# SenseGrain_v0_1.net
KiCad netlist of a schematic drawn in EAGLE
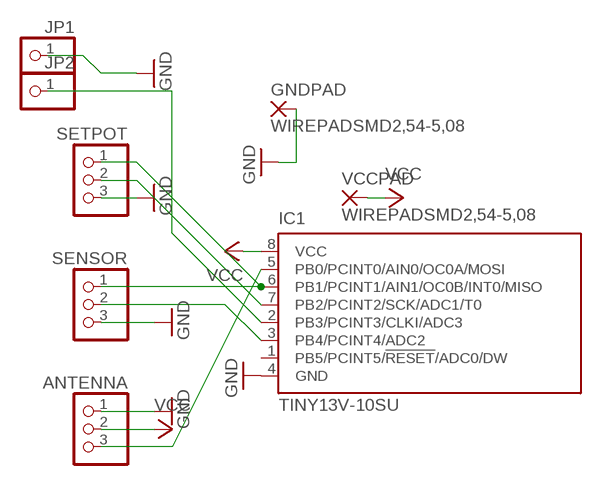
[diagram p0: schematic, sheet 1]

(export (version "E")
  (design (tool "Eeschema 10.0.6"))
  (components
    (comp (ref "ANTENNA")
      (value "PINHD-1X3CB")
      (footprint "eagle-import:1X03-CLEANBIG")
      (libsource (lib "eagle-import") (part "PINHD-1X3CB"))
    )
    (comp (ref "GNDPAD")
      (value "WIREPADSMD2,54-5,08")
      (footprint "eagle-import:SMD2,54-5,08")
      (libsource (lib "eagle-import") (part "WIREPADSMD2,54-5,08"))
    )
    (comp (ref "IC1")
      (value "TINY13V-10SU")
      (footprint "eagle-import:8S2")
      (fields (field (name "MPN") "ATTINY13V-10SU"))
      (libsource (lib "eagle-import") (part "TINY13SUV-10"))
    )
    (comp (ref "JP1")
      (value "PINHD-1X1")
      (footprint "eagle-import:1X01")
      (libsource (lib "eagle-import") (part "PINHD-1X1"))
    )
    (comp (ref "JP2")
      (value "PINHD-1X1")
      (footprint "eagle-import:1X01")
      (libsource (lib "eagle-import") (part "PINHD-1X1"))
    )
    (comp (ref "SENSOR")
      (value "PINHD-1X3CB")
      (footprint "eagle-import:1X03-CLEANBIG")
      (libsource (lib "eagle-import") (part "PINHD-1X3CB"))
    )
    (comp (ref "SETPOT")
      (value "PINHD-1X3CB")
      (footprint "eagle-import:1X03-CLEANBIG")
      (libsource (lib "eagle-import") (part "PINHD-1X3CB"))
    )
    (comp (ref "VCCPAD")
      (value "WIREPADSMD2,54-5,08")
      (footprint "eagle-import:SMD2,54-5,08")
      (libsource (lib "eagle-import") (part "WIREPADSMD2,54-5,08"))
    )
  )
  (nets
    (net (code "1") (name "GND") (class "Default")
      (node (ref "ANTENNA") (pin "1") (pinfunction "1_1") (pintype "passive"))
      (node (ref "GNDPAD") (pin "1") (pinfunction "P_1") (pintype "passive"))
      (node (ref "IC1") (pin "4") (pinfunction "GND_4") (pintype "power_in"))
      (node (ref "JP1") (pin "1") (pinfunction "1_1") (pintype "passive"))
      (node (ref "SENSOR") (pin "3") (pinfunction "3_3") (pintype "passive"))
      (node (ref "SETPOT") (pin "3") (pinfunction "3_3") (pintype "passive"))
    )
    (net (code "2") (name "Net-(IC1-PB0{slash}PCINT0{slash}AIN0{slash}OC0A{slash}MOSI)") (class "Default")
      (node (ref "ANTENNA") (pin "3") (pinfunction "3_3") (pintype "passive"))
      (node (ref "IC1") (pin "5") (pinfunction "PB0/PCINT0/AIN0/OC0A/MOSI_5") (pintype "bidirectional"))
    )
    (net (code "3") (name "Net-(IC1-PB1{slash}PCINT1{slash}AIN1{slash}OC0B{slash}INT0{slash}MISO)") (class "Default")
      (node (ref "IC1") (pin "6") (pinfunction "PB1/PCINT1/AIN1/OC0B/INT0/MISO_6") (pintype "bidirectional"))
      (node (ref "SENSOR") (pin "1") (pinfunction "1_1") (pintype "passive"))
      (node (ref "SETPOT") (pin "1") (pinfunction "1_1") (pintype "passive"))
    )
    (net (code "4") (name "Net-(IC1-PB2{slash}PCINT2{slash}SCK{slash}ADC1{slash}T0)") (class "Default")
      (node (ref "IC1") (pin "7") (pinfunction "PB2/PCINT2/SCK/ADC1/T0_7") (pintype "bidirectional"))
      (node (ref "SETPOT") (pin "2") (pinfunction "2_2") (pintype "passive"))
    )
    (net (code "5") (name "Net-(IC1-PB3{slash}PCINT3{slash}CLKI{slash}ADC3)") (class "Default")
      (node (ref "IC1") (pin "2") (pinfunction "PB3/PCINT3/CLKI/ADC3_2") (pintype "bidirectional"))
      (node (ref "JP2") (pin "1") (pinfunction "1_1") (pintype "passive"))
    )
    (net (code "6") (name "Net-(IC1-PB4{slash}PCINT4{slash}ADC2)") (class "Default")
      (node (ref "IC1") (pin "3") (pinfunction "PB4/PCINT4/ADC2_3") (pintype "bidirectional"))
      (node (ref "SENSOR") (pin "2") (pinfunction "2_2") (pintype "passive"))
    )
    (net (code "7") (name "VCC") (class "Default")
      (node (ref "ANTENNA") (pin "2") (pinfunction "2_2") (pintype "passive"))
      (node (ref "IC1") (pin "8") (pinfunction "VCC_8") (pintype "power_in"))
      (node (ref "VCCPAD") (pin "1") (pinfunction "P_1") (pintype "passive"))
    )
    (net (code "8") (name "unconnected-(IC1-PB5{slash}PCINT5{slash}~{RESET}{slash}ADC0{slash}DW-Pad1)") (class "Default")
      (node (ref "IC1") (pin "1") (pinfunction "PB5/PCINT5/~{RESET}/ADC0/DW_1") (pintype "bidirectional"))
    )
  )
)
